# CYD-pcb-v4-buffer-Castellated.net
KiCad netlist of a schematic drawn in EAGLE
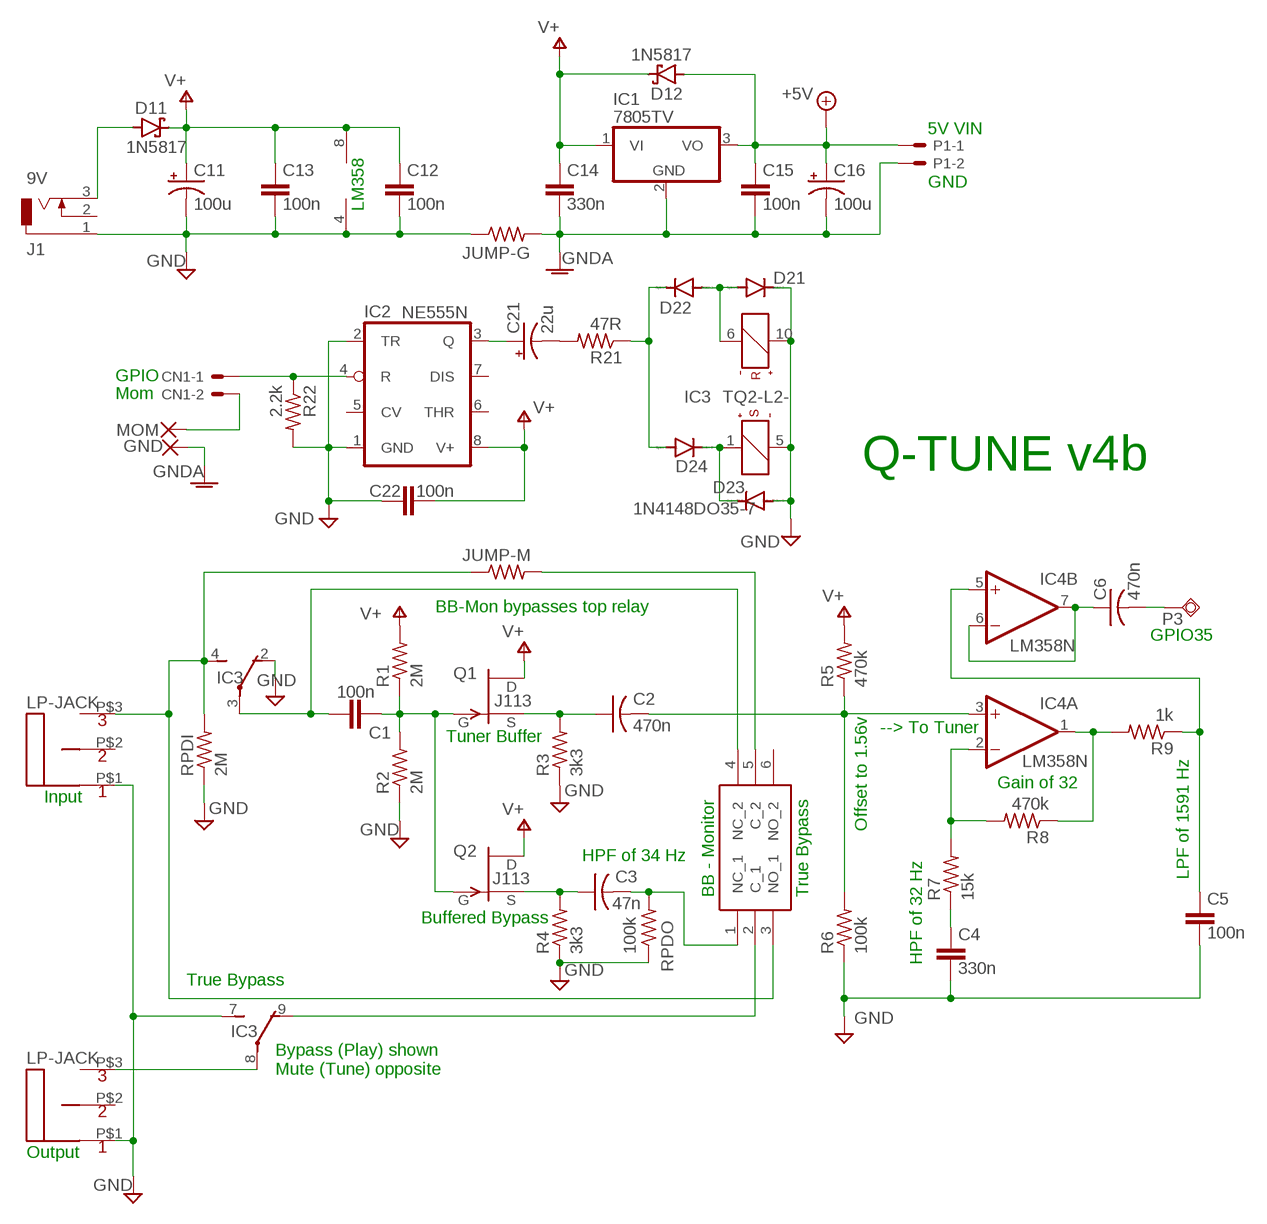
[diagram p0: schematic, sheet 1]

(export (version "E")
  (design (tool "Eeschema 10.0.6"))
  (components
    (comp (ref "C1")
      (value "100n")
      (footprint "eagle-import:C050-024X044")
      (libsource (lib "eagle-import") (part "C-EU050-024X044"))
    )
    (comp (ref "C2")
      (value "470n")
      (footprint "eagle-import:C050-035X075")
      (libsource (lib "eagle-import") (part "C-US050-035X075"))
    )
    (comp (ref "C3")
      (value "47n")
      (footprint "eagle-import:C050-035X075")
      (libsource (lib "eagle-import") (part "C-US050-035X075"))
    )
    (comp (ref "C4")
      (value "330n")
      (footprint "eagle-import:C050-024X044")
      (libsource (lib "eagle-import") (part "C-EU050-024X044"))
    )
    (comp (ref "C5")
      (value "100n")
      (footprint "eagle-import:C050-024X044")
      (libsource (lib "eagle-import") (part "C-EU050-024X044"))
    )
    (comp (ref "C6")
      (value "470n")
      (footprint "eagle-import:C050-035X075")
      (libsource (lib "eagle-import") (part "C-US050-035X075"))
    )
    (comp (ref "C11")
      (value "100u")
      (footprint "eagle-import:E2,5-6")
      (libsource (lib "eagle-import") (part "CPOL-USE2.5-6"))
    )
    (comp (ref "C12")
      (value "100n")
      (footprint "eagle-import:C050-024X044")
      (libsource (lib "eagle-import") (part "C-EU050-024X044"))
    )
    (comp (ref "C13")
      (value "100n")
      (footprint "eagle-import:C050-024X044")
      (libsource (lib "eagle-import") (part "C-EU050-024X044"))
    )
    (comp (ref "C14")
      (value "330n")
      (footprint "eagle-import:C050-024X044")
      (libsource (lib "eagle-import") (part "C-EU050-024X044"))
    )
    (comp (ref "C15")
      (value "100n")
      (footprint "eagle-import:C050-024X044")
      (libsource (lib "eagle-import") (part "C-EU050-024X044"))
    )
    (comp (ref "C16")
      (value "100u")
      (footprint "eagle-import:E2,5-6")
      (libsource (lib "eagle-import") (part "CPOL-USE2.5-6"))
    )
    (comp (ref "C21")
      (value "22u")
      (footprint "eagle-import:E2,5-6")
      (libsource (lib "eagle-import") (part "CPOL-USE2.5-6"))
    )
    (comp (ref "C22")
      (value "100n")
      (footprint "eagle-import:C050-024X044")
      (libsource (lib "eagle-import") (part "C-EU050-024X044"))
    )
    (comp (ref "CN1")
      (value "22-23-2021")
      (footprint "eagle-import:22-23-2021")
      (fields (field (name "MF") "MOLEX"))
      (libsource (lib "eagle-import") (part "22-23-2021"))
    )
    (comp (ref "D11")
      (value "1N5817")
      (footprint "eagle-import:DO41-7.6")
      (libsource (lib "eagle-import") (part "1N5819-B"))
    )
    (comp (ref "D12")
      (value "1N5817")
      (footprint "eagle-import:DO41-7.6")
      (libsource (lib "eagle-import") (part "1N5819-B"))
    )
    (comp (ref "D21")
      (value "1N4148DO35-7")
      (footprint "eagle-import:DO35-7")
      (libsource (lib "eagle-import") (part "1N4148DO35-7"))
    )
    (comp (ref "D22")
      (value "1N4148DO35-7")
      (footprint "eagle-import:DO35-7")
      (libsource (lib "eagle-import") (part "1N4148DO35-7"))
    )
    (comp (ref "D23")
      (value "1N4148DO35-7")
      (footprint "eagle-import:DO35-7")
      (libsource (lib "eagle-import") (part "1N4148DO35-7"))
    )
    (comp (ref "D24")
      (value "1N4148DO35-7")
      (footprint "eagle-import:DO35-7")
      (libsource (lib "eagle-import") (part "1N4148DO35-7"))
    )
    (comp (ref "GND")
      (value "WIREPAD1,6/0,9")
      (footprint "eagle-import:1,6_0,9")
      (libsource (lib "eagle-import") (part "WIREPAD1,6/0,9"))
    )
    (comp (ref "IC1")
      (value "7805TV")
      (footprint "eagle-import:TO220V")
      (libsource (lib "eagle-import") (part "78TV05"))
    )
    (comp (ref "IC2")
      (value "NE555N")
      (footprint "eagle-import:DIL08")
      (libsource (lib "eagle-import") (part "555NNE"))
    )
    (comp (ref "IC3")
      (value "TQ2-L2-")
      (footprint "eagle-import:TQ2")
      (fields (field (name "MF") "AROMAT/ MATSUSHITA") (field (name "MPN") "TQ2-L2-9V"))
      (libsource (lib "eagle-import") (part "TQ2?-L2-"))
    )
    (comp (ref "IC4")
      (value "LM358N")
      (footprint "eagle-import:DIL08")
      (libsource (lib "eagle-import") (part "LM358N"))
    )
    (comp (ref "INPUTJACK")
      (value "LPJACK-DEVICE")
      (footprint "eagle-import:LPJACK-FOOTPRINT")
      (libsource (lib "eagle-import") (part "LPJACK-DEVICE"))
    )
    (comp (ref "J1")
      (value "9V")
      (footprint "eagle-import:DCJ0303")
      (libsource (lib "eagle-import") (part "DCJ0303"))
    )
    (comp (ref "JUMP-G")
      (value "*")
      (footprint "eagle-import:0207_7")
      (libsource (lib "eagle-import") (part "R-US_0207/7"))
    )
    (comp (ref "JUMP-M")
      (value "1")
      (footprint "eagle-import:0207_7")
      (libsource (lib "eagle-import") (part "R-US_0207/7"))
    )
    (comp (ref "MOM")
      (value "WIREPAD1,6/0,9")
      (footprint "eagle-import:1,6_0,9")
      (libsource (lib "eagle-import") (part "WIREPAD1,6/0,9"))
    )
    (comp (ref "OUTPUTJACK")
      (value "LPJACK-DEVICE")
      (footprint "eagle-import:LPJACK-FOOTPRINT")
      (libsource (lib "eagle-import") (part "LPJACK-DEVICE"))
    )
    (comp (ref "P1")
      (value "22-23-2021")
      (footprint "eagle-import:22-23-2021")
      (fields (field (name "MF") "MOLEX"))
      (libsource (lib "eagle-import") (part "22-23-2021"))
    )
    (comp (ref "P3")
      (value "TPSQPAD1-13Y")
      (footprint "eagle-import:P1-13Y")
      (libsource (lib "eagle-import") (part "TPSQPAD1-13Y"))
    )
    (comp (ref "Q1")
      (value "J113")
      (footprint "eagle-import:TO92-")
      (libsource (lib "eagle-import") (part "?5482N4"))
    )
    (comp (ref "Q2")
      (value "J113")
      (footprint "eagle-import:TO92-")
      (libsource (lib "eagle-import") (part "?5482N4"))
    )
    (comp (ref "R1")
      (value "2M")
      (footprint "eagle-import:0207_7")
      (libsource (lib "eagle-import") (part "R-US_0207/7"))
    )
    (comp (ref "R2")
      (value "2M")
      (footprint "eagle-import:0207_7")
      (libsource (lib "eagle-import") (part "R-US_0207/7"))
    )
    (comp (ref "R3")
      (value "3k3")
      (footprint "eagle-import:0207_7")
      (libsource (lib "eagle-import") (part "R-US_0207/7"))
    )
    (comp (ref "R4")
      (value "3k3")
      (footprint "eagle-import:0207_7")
      (libsource (lib "eagle-import") (part "R-US_0207/7"))
    )
    (comp (ref "R5")
      (value "470k")
      (footprint "eagle-import:0207_7")
      (libsource (lib "eagle-import") (part "R-US_0207/7"))
    )
    (comp (ref "R6")
      (value "100k")
      (footprint "eagle-import:0207_7")
      (libsource (lib "eagle-import") (part "R-US_0207/7"))
    )
    (comp (ref "R7")
      (value "15k")
      (footprint "eagle-import:0207_7")
      (libsource (lib "eagle-import") (part "R-US_0207/7"))
    )
    (comp (ref "R8")
      (value "470k")
      (footprint "eagle-import:0207_7")
      (libsource (lib "eagle-import") (part "R-US_0207/7"))
    )
    (comp (ref "R9")
      (value "1k")
      (footprint "eagle-import:0207_7")
      (libsource (lib "eagle-import") (part "R-US_0207/7"))
    )
    (comp (ref "R21")
      (value "47R")
      (footprint "eagle-import:0207_7")
      (libsource (lib "eagle-import") (part "R-US_0207/7"))
    )
    (comp (ref "R22")
      (value "2.2k")
      (footprint "eagle-import:0207_7")
      (libsource (lib "eagle-import") (part "R-US_0207/7"))
    )
    (comp (ref "RPDI")
      (value "2M")
      (footprint "eagle-import:0207_7")
      (libsource (lib "eagle-import") (part "R-US_0207/7"))
    )
    (comp (ref "RPDO")
      (value "100k")
      (footprint "eagle-import:0207_7")
      (libsource (lib "eagle-import") (part "R-US_0207/7"))
    )
    (comp (ref "SW1")
      (value "JS202011AQN")
      (footprint "eagle-import:JS202011AQN")
      (fields (field (name "MOUSER_PART_NUMBER") "611-JS202011AQN"))
      (libsource (lib "eagle-import") (part "JS202011AQN"))
    )
  )
  (nets
    (net (code "1") (name "+5V") (class "Default")
      (node (ref "C15") (pin "1") (pinfunction "1_1") (pintype "passive"))
      (node (ref "C16") (pin "+") (pinfunction "+_+") (pintype "passive"))
      (node (ref "D12") (pin "A") (pinfunction "A_A") (pintype "passive"))
      (node (ref "IC1") (pin "3") (pinfunction "VO_3") (pintype "passive"))
      (node (ref "P1") (pin "1") (pinfunction "S_1") (pintype "passive"))
    )
    (net (code "2") (name "GND") (class "Default")
      (node (ref "C11") (pin "-") (pinfunction "-_-") (pintype "passive"))
      (node (ref "C12") (pin "2") (pinfunction "2_2") (pintype "passive"))
      (node (ref "C13") (pin "2") (pinfunction "2_2") (pintype "passive"))
      (node (ref "C22") (pin "1") (pinfunction "1_1") (pintype "passive"))
      (node (ref "C4") (pin "2") (pinfunction "2_2") (pintype "passive"))
      (node (ref "C5") (pin "2") (pinfunction "2_2") (pintype "passive"))
      (node (ref "D21") (pin "C") (pinfunction "C_C") (pintype "passive"))
      (node (ref "D23") (pin "A") (pinfunction "A_A") (pintype "passive"))
      (node (ref "IC2") (pin "1") (pinfunction "GND_1") (pintype "power_in"))
      (node (ref "IC2") (pin "2") (pinfunction "TR_2") (pintype "input"))
      (node (ref "IC3") (pin "10") (pinfunction "+_10") (pintype "passive"))
      (node (ref "IC3") (pin "2") (pinfunction "O_2") (pintype "passive"))
      (node (ref "IC3") (pin "5") (pinfunction "-_5") (pintype "passive"))
      (node (ref "IC3") (pin "7") (pinfunction "S_7") (pintype "passive"))
      (node (ref "IC4") (pin "4") (pinfunction "V-_4") (pintype "power_in"))
      (node (ref "INPUTJACK") (pin "P$1") (pinfunction "1_P$1") (pintype "bidirectional"))
      (node (ref "J1") (pin "1") (pinfunction "1_1") (pintype "passive"))
      (node (ref "JUMP-G") (pin "1") (pinfunction "1_1") (pintype "passive"))
      (node (ref "OUTPUTJACK") (pin "P$1") (pinfunction "1_P$1") (pintype "bidirectional"))
      (node (ref "R2") (pin "1") (pinfunction "1_1") (pintype "passive"))
      (node (ref "R22") (pin "2") (pinfunction "2_2") (pintype "passive"))
      (node (ref "R3") (pin "1") (pinfunction "1_1") (pintype "passive"))
      (node (ref "R4") (pin "1") (pinfunction "1_1") (pintype "passive"))
      (node (ref "R6") (pin "1") (pinfunction "1_1") (pintype "passive"))
      (node (ref "RPDI") (pin "1") (pinfunction "1_1") (pintype "passive"))
      (node (ref "RPDO") (pin "1") (pinfunction "1_1") (pintype "passive"))
    )
    (net (code "3") (name "GNDA") (class "Default")
      (node (ref "C14") (pin "2") (pinfunction "2_2") (pintype "passive"))
      (node (ref "C15") (pin "2") (pinfunction "2_2") (pintype "passive"))
      (node (ref "C16") (pin "-") (pinfunction "-_-") (pintype "passive"))
      (node (ref "GND") (pin "1") (pinfunction "P_1") (pintype "passive"))
      (node (ref "IC1") (pin "2") (pinfunction "GND_2") (pintype "passive"))
      (node (ref "JUMP-G") (pin "2") (pinfunction "2_2") (pintype "passive"))
      (node (ref "P1") (pin "2") (pinfunction "S_2") (pintype "passive"))
    )
    (net (code "4") (name "Net-(C4-Pad1)") (class "Default")
      (node (ref "C4") (pin "1") (pinfunction "1_1") (pintype "passive"))
      (node (ref "R7") (pin "1") (pinfunction "1_1") (pintype "passive"))
    )
    (net (code "5") (name "Net-(C6-Pad2)") (class "Default")
      (node (ref "C6") (pin "2") (pinfunction "2_2") (pintype "passive"))
      (node (ref "P3") (pin "TP") (pinfunction "TP_TP") (pintype "input"))
    )
    (net (code "6") (name "Net-(C21-Pad-)") (class "Default")
      (node (ref "C21") (pin "-") (pinfunction "-_-") (pintype "passive"))
      (node (ref "R21") (pin "2") (pinfunction "2_2") (pintype "passive"))
    )
    (net (code "7") (name "Net-(CN1A-S)") (class "Default")
      (node (ref "CN1") (pin "1") (pinfunction "S_1") (pintype "passive"))
      (node (ref "IC2") (pin "4") (pinfunction "R_4") (pintype "input"))
      (node (ref "R22") (pin "1") (pinfunction "1_1") (pintype "passive"))
    )
    (net (code "8") (name "Net-(CN1B-S)") (class "Default")
      (node (ref "CN1") (pin "2") (pinfunction "S_2") (pintype "passive"))
      (node (ref "MOM") (pin "1") (pinfunction "P_1") (pintype "passive"))
    )
    (net (code "9") (name "Net-(D11-PadA)") (class "Default")
      (node (ref "D11") (pin "A") (pinfunction "A_A") (pintype "passive"))
      (node (ref "J1") (pin "3") (pinfunction "3_3") (pintype "passive"))
    )
    (net (code "10") (name "Net-(D22-PadC)") (class "Default")
      (node (ref "D22") (pin "C") (pinfunction "C_C") (pintype "passive"))
      (node (ref "D24") (pin "A") (pinfunction "A_A") (pintype "passive"))
      (node (ref "R21") (pin "1") (pinfunction "1_1") (pintype "passive"))
    )
    (net (code "11") (name "Net-(IC2-Q)") (class "Default")
      (node (ref "C21") (pin "+") (pinfunction "+_+") (pintype "passive"))
      (node (ref "IC2") (pin "3") (pinfunction "Q_3") (pintype "output"))
    )
    (net (code "12") (name "Net-(IC3A-P)") (class "Default")
      (node (ref "C1") (pin "2") (pinfunction "2_2") (pintype "passive"))
      (node (ref "IC3") (pin "3") (pinfunction "P_3") (pintype "passive"))
      (node (ref "SW1") (pin "4") (pinfunction "NC_2_4") (pintype "bidirectional"))
    )
    (net (code "13") (name "Net-(IC3A-S)") (class "Default")
      (node (ref "IC3") (pin "4") (pinfunction "S_4") (pintype "passive"))
      (node (ref "INPUTJACK") (pin "P$3") (pinfunction "3_P$3") (pintype "bidirectional"))
      (node (ref "JUMP-M") (pin "1") (pinfunction "1_1") (pintype "passive"))
      (node (ref "RPDI") (pin "2") (pinfunction "2_2") (pintype "passive"))
      (node (ref "SW1") (pin "3") (pinfunction "NO_1_3") (pintype "bidirectional"))
    )
    (net (code "14") (name "Net-(IC3B-O)") (class "Default")
      (node (ref "IC3") (pin "9") (pinfunction "O_9") (pintype "passive"))
      (node (ref "SW1") (pin "2") (pinfunction "C_1_2") (pintype "bidirectional"))
    )
    (net (code "15") (name "Net-(IC3B-P)") (class "Default")
      (node (ref "IC3") (pin "8") (pinfunction "P_8") (pintype "passive"))
      (node (ref "OUTPUTJACK") (pin "P$3") (pinfunction "3_P$3") (pintype "bidirectional"))
    )
    (net (code "16") (name "Net-(IC3C--)") (class "Default")
      (node (ref "D21") (pin "A") (pinfunction "A_A") (pintype "passive"))
      (node (ref "D22") (pin "A") (pinfunction "A_A") (pintype "passive"))
      (node (ref "IC3") (pin "6") (pinfunction "-_6") (pintype "passive"))
    )
    (net (code "17") (name "Net-(IC3D-+)") (class "Default")
      (node (ref "D23") (pin "C") (pinfunction "C_C") (pintype "passive"))
      (node (ref "D24") (pin "C") (pinfunction "C_C") (pintype "passive"))
      (node (ref "IC3") (pin "1") (pinfunction "+_1") (pintype "passive"))
    )
    (net (code "18") (name "Net-(IC4A-+IN)") (class "Default")
      (node (ref "C2") (pin "2") (pinfunction "2_2") (pintype "passive"))
      (node (ref "IC4") (pin "3") (pinfunction "+IN_3") (pintype "input"))
      (node (ref "R5") (pin "1") (pinfunction "1_1") (pintype "passive"))
      (node (ref "R6") (pin "2") (pinfunction "2_2") (pintype "passive"))
    )
    (net (code "19") (name "Net-(IC4A--IN)") (class "Default")
      (node (ref "IC4") (pin "2") (pinfunction "-IN_2") (pintype "input"))
      (node (ref "R7") (pin "2") (pinfunction "2_2") (pintype "passive"))
      (node (ref "R8") (pin "2") (pinfunction "2_2") (pintype "passive"))
    )
    (net (code "20") (name "Net-(IC4A-OUT)") (class "Default")
      (node (ref "IC4") (pin "1") (pinfunction "OUT_1") (pintype "output"))
      (node (ref "R8") (pin "1") (pinfunction "1_1") (pintype "passive"))
      (node (ref "R9") (pin "2") (pinfunction "2_2") (pintype "passive"))
    )
    (net (code "21") (name "Net-(IC4B-+IN)") (class "Default")
      (node (ref "C5") (pin "1") (pinfunction "1_1") (pintype "passive"))
      (node (ref "IC4") (pin "5") (pinfunction "+IN_5") (pintype "input"))
      (node (ref "R9") (pin "1") (pinfunction "1_1") (pintype "passive"))
    )
    (net (code "22") (name "Net-(IC4B--IN)") (class "Default")
      (node (ref "C6") (pin "1") (pinfunction "1_1") (pintype "passive"))
      (node (ref "IC4") (pin "6") (pinfunction "-IN_6") (pintype "input"))
      (node (ref "IC4") (pin "7") (pinfunction "OUT_7") (pintype "output"))
    )
    (net (code "23") (name "Net-(Q1-G)") (class "Default")
      (node (ref "C1") (pin "1") (pinfunction "1_1") (pintype "passive"))
      (node (ref "Q1") (pin "1") (pinfunction "G_1") (pintype "passive"))
      (node (ref "Q2") (pin "1") (pinfunction "G_1") (pintype "passive"))
      (node (ref "R1") (pin "1") (pinfunction "1_1") (pintype "passive"))
      (node (ref "R2") (pin "2") (pinfunction "2_2") (pintype "passive"))
    )
    (net (code "24") (name "Net-(Q1-S)") (class "Default")
      (node (ref "C2") (pin "1") (pinfunction "1_1") (pintype "passive"))
      (node (ref "Q1") (pin "2") (pinfunction "S_2") (pintype "passive"))
      (node (ref "R3") (pin "2") (pinfunction "2_2") (pintype "passive"))
    )
    (net (code "25") (name "Net-(Q2-S)") (class "Default")
      (node (ref "C3") (pin "1") (pinfunction "1_1") (pintype "passive"))
      (node (ref "Q2") (pin "2") (pinfunction "S_2") (pintype "passive"))
      (node (ref "R4") (pin "2") (pinfunction "2_2") (pintype "passive"))
    )
    (net (code "26") (name "Net-(SW1-C_2)") (class "Default")
      (node (ref "JUMP-M") (pin "2") (pinfunction "2_2") (pintype "passive"))
      (node (ref "SW1") (pin "5") (pinfunction "C_2_5") (pintype "bidirectional"))
    )
    (net (code "27") (name "Net-(SW1-NC_1)") (class "Default")
      (node (ref "C3") (pin "2") (pinfunction "2_2") (pintype "passive"))
      (node (ref "RPDO") (pin "2") (pinfunction "2_2") (pintype "passive"))
      (node (ref "SW1") (pin "1") (pinfunction "NC_1_1") (pintype "bidirectional"))
    )
    (net (code "28") (name "V+") (class "Default")
      (node (ref "C11") (pin "+") (pinfunction "+_+") (pintype "passive"))
      (node (ref "C12") (pin "1") (pinfunction "1_1") (pintype "passive"))
      (node (ref "C13") (pin "1") (pinfunction "1_1") (pintype "passive"))
      (node (ref "C14") (pin "1") (pinfunction "1_1") (pintype "passive"))
      (node (ref "C22") (pin "2") (pinfunction "2_2") (pintype "passive"))
      (node (ref "D11") (pin "C") (pinfunction "C_C") (pintype "passive"))
      (node (ref "D12") (pin "C") (pinfunction "C_C") (pintype "passive"))
      (node (ref "IC1") (pin "1") (pinfunction "VI_1") (pintype "input"))
      (node (ref "IC2") (pin "8") (pinfunction "V+_8") (pintype "power_in"))
      (node (ref "IC4") (pin "8") (pinfunction "V+_8") (pintype "power_in"))
      (node (ref "Q1") (pin "3") (pinfunction "D_3") (pintype "passive"))
      (node (ref "Q2") (pin "3") (pinfunction "D_3") (pintype "passive"))
      (node (ref "R1") (pin "2") (pinfunction "2_2") (pintype "passive"))
      (node (ref "R5") (pin "2") (pinfunction "2_2") (pintype "passive"))
    )
    (net (code "29") (name "unconnected-(IC2-CV-Pad5)") (class "Default")
      (node (ref "IC2") (pin "5") (pinfunction "CV_5") (pintype "input"))
    )
    (net (code "30") (name "unconnected-(IC2-DIS-Pad7)") (class "Default")
      (node (ref "IC2") (pin "7") (pinfunction "DIS_7") (pintype "input"))
    )
    (net (code "31") (name "unconnected-(IC2-THR-Pad6)") (class "Default")
      (node (ref "IC2") (pin "6") (pinfunction "THR_6") (pintype "input"))
    )
    (net (code "32") (name "unconnected-(INPUTJACK-2-PadP$2)") (class "Default")
      (node (ref "INPUTJACK") (pin "P$2") (pinfunction "2_P$2") (pintype "bidirectional"))
    )
    (net (code "33") (name "unconnected-(J1-Pad2)") (class "Default")
      (node (ref "J1") (pin "2") (pinfunction "2_2") (pintype "passive"))
    )
    (net (code "34") (name "unconnected-(OUTPUTJACK-2-PadP$2)") (class "Default")
      (node (ref "OUTPUTJACK") (pin "P$2") (pinfunction "2_P$2") (pintype "bidirectional"))
    )
    (net (code "35") (name "unconnected-(SW1-NO_2-Pad6)") (class "Default")
      (node (ref "SW1") (pin "6") (pinfunction "NO_2_6") (pintype "bidirectional"))
    )
  )
)
